# H204_R_Power.net
KiCad netlist of a schematic drawn in Altium Designer
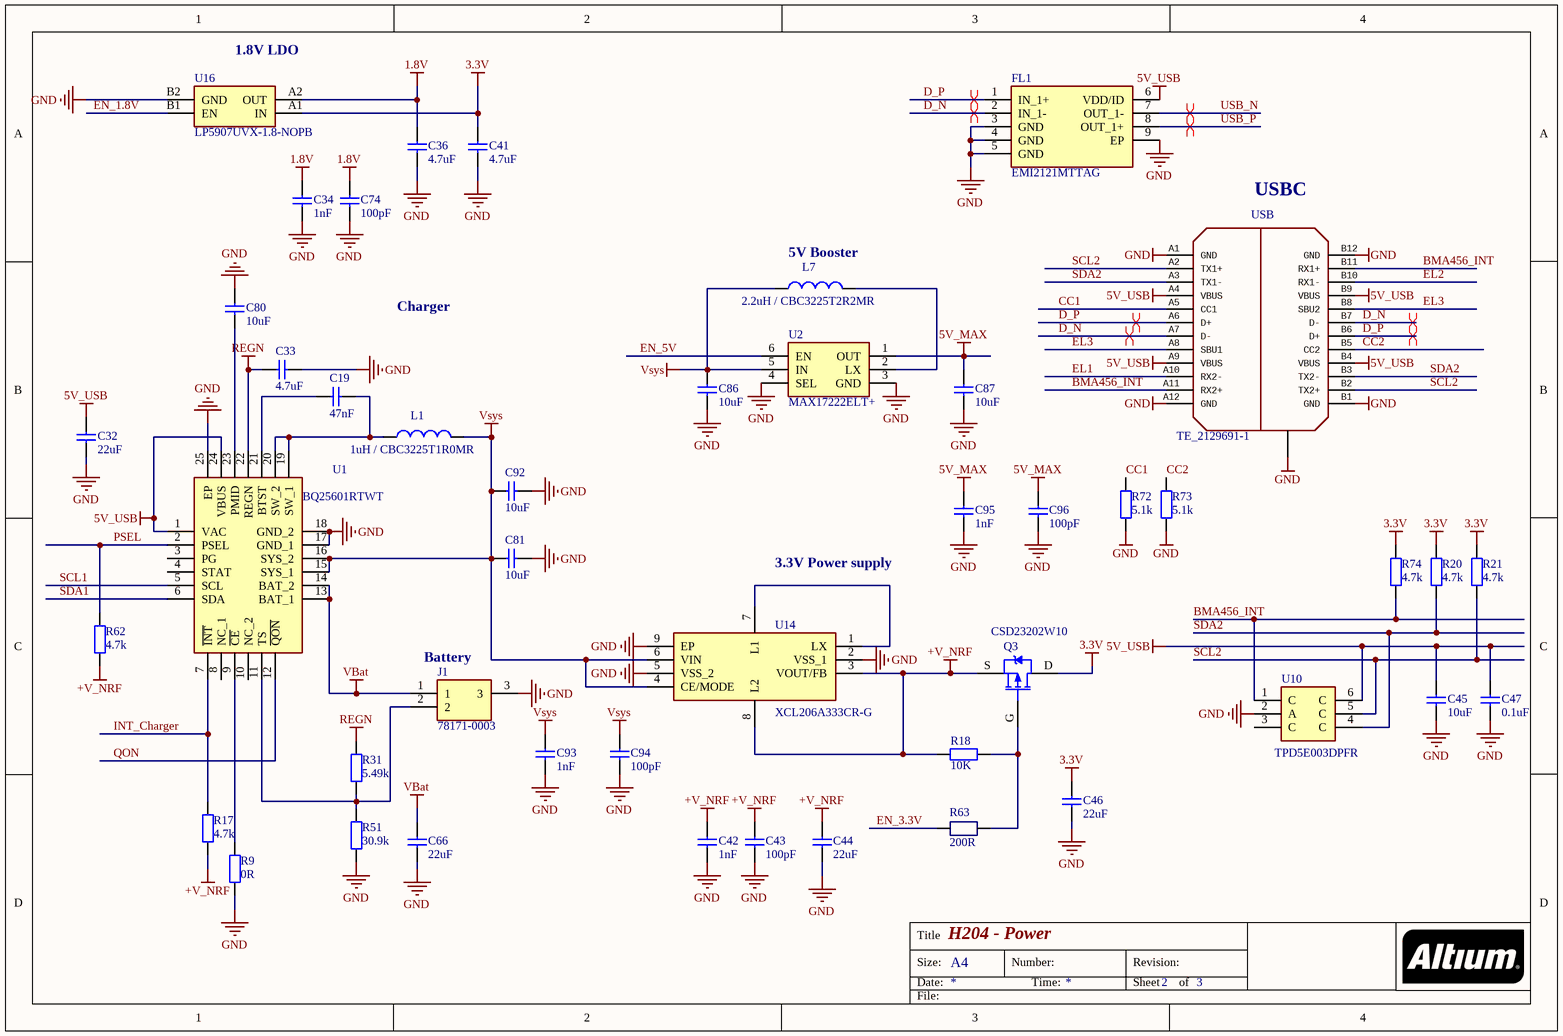
[diagram p0: H204_R_Power.SchDoc]

(export (version "E")
  (design (tool "Eeschema 10.0.6"))
  (components
    (comp (ref "C19")
      (value "47nF")
      (footprint "CAPC0603X33N")
      (description "CAP CER 0.047UF 25V X5R 0201")
      (fields
        (field (name "MANUFACTURER") "TDK")
        (field (name "MANUFACTURER PART NUMBER") "C0603X5R1E473K030BB")
      )
      (libsource (lib "Nordic Passive DB") (part "CAP"))
    )
    (comp (ref "C32")
      (value "22uF")
      (footprint "CAPC1005X55N")
      (description "CAP CER 22UF 6.3V X5R 0402")
      (fields
        (field (name "MANUFACTURER") "Samsung")
        (field (name "MANUFACTURER PART NUMBER") "CL05A226MQ5QUNC")
      )
      (libsource (lib "Nordic Passive DB") (part "CAP"))
    )
    (comp (ref "C33")
      (value "4.7uF")
      (footprint "CAPC1005X55N")
      (description "Cap Ceramic 4.7uF 16V X5R 20% SMD 0402 85C T/R")
      (fields
        (field (name "MANUFACTURER") "Samsung")
        (field (name "MANUFACTURER PART NUMBER") "CL05A475MO5NUNC")
      )
      (libsource (lib "Nordic Passive DB") (part "CAP"))
    )
    (comp (ref "C34")
      (value "1nF")
      (footprint "CAPC0603X33N")
      (description "Cap Ceramic 0.001uF 25V X7R 10% SMD 0201 125C Paper T/R")
      (fields
        (field (name "MANUFACTURER") "Samsung")
        (field (name "MANUFACTURER PART NUMBER") "CL03B102KA3NNNC")
      )
      (libsource (lib "Nordic Passive DB") (part "CAP"))
    )
    (comp (ref "C36")
      (value "4.7uF")
      (footprint "CAPC1005X55N")
      (description "Cap Ceramic 4.7uF 16V X5R 20% SMD 0402 85C T/R")
      (fields
        (field (name "MANUFACTURER") "Samsung")
        (field (name "MANUFACTURER PART NUMBER") "CL05A475MO5NUNC")
      )
      (libsource (lib "Nordic Passive DB") (part "CAP"))
    )
    (comp (ref "C41")
      (value "4.7uF")
      (footprint "CAPC1005X55N")
      (description "Cap Ceramic 4.7uF 16V X5R 20% SMD 0402 85C T/R")
      (fields
        (field (name "MANUFACTURER") "Samsung")
        (field (name "MANUFACTURER PART NUMBER") "CL05A475MO5NUNC")
      )
      (libsource (lib "Nordic Passive DB") (part "CAP"))
    )
    (comp (ref "C42")
      (value "1nF")
      (footprint "CAPC0603X33N")
      (description "Cap Ceramic 0.001uF 25V X7R 10% SMD 0201 125C Paper T/R")
      (fields
        (field (name "MANUFACTURER") "Samsung")
        (field (name "MANUFACTURER PART NUMBER") "CL03B102KA3NNNC")
      )
      (libsource (lib "Nordic Passive DB") (part "CAP"))
    )
    (comp (ref "C43")
      (value "100pF")
      (footprint "CAPC0603X33N")
      (description "CAP CER 100PF 50V C0G 0201")
      (fields
        (field (name "MANUFACTURER") "TDK")
        (field (name "MANUFACTURER PART NUMBER") "C0603C0G1H101J030BA")
      )
      (libsource (lib "Nordic Passive DB") (part "CAP"))
    )
    (comp (ref "C44")
      (value "22uF")
      (footprint "CAPC1005X55N")
      (description "CAP CER 22UF 6.3V X5R 0402")
      (fields
        (field (name "MANUFACTURER") "Samsung")
        (field (name "MANUFACTURER PART NUMBER") "CL05A226MQ5QUNC")
      )
      (libsource (lib "Nordic Passive DB") (part "CAP"))
    )
    (comp (ref "C45")
      (value "10uF")
      (footprint "CAPC1005X55N")
      (description "CAP CER 10UF 10V X5R 0402")
      (fields
        (field (name "MANUFACTURER") "Samsung")
        (field (name "MANUFACTURER PART NUMBER") "CL05A106MP8NUB8")
      )
      (libsource (lib "Nordic Passive DB") (part "CAP"))
    )
    (comp (ref "C46")
      (value "22uF")
      (footprint "CAPC1005X55N")
      (description "CAP CER 22UF 6.3V X5R 0402")
      (fields
        (field (name "MANUFACTURER") "Samsung")
        (field (name "MANUFACTURER PART NUMBER") "CL05A226MQ5QUNC")
      )
      (libsource (lib "Nordic Passive DB") (part "CAP"))
    )
    (comp (ref "C47")
      (value "0.1uF")
      (footprint "CAPC0603X33N")
      (description "CAP CER 0.1UF 16V X5R 0201")
      (fields
        (field (name "MANUFACTURER") "Samsung")
        (field (name "MANUFACTURER PART NUMBER") "CL03A104KO3NNNC")
      )
      (libsource (lib "AltiumLib") (part "CAP"))
    )
    (comp (ref "C66")
      (value "22uF")
      (footprint "CAPC1005X55N")
      (description "CAP CER 22UF 6.3V X5R 0402")
      (fields
        (field (name "MANUFACTURER") "Samsung")
        (field (name "MANUFACTURER PART NUMBER") "CL05A226MQ5QUNC")
      )
      (libsource (lib "Nordic Passive DB") (part "CAP"))
    )
    (comp (ref "C74")
      (value "100pF")
      (footprint "CAPC0603X33N")
      (description "CAP CER 100PF 50V C0G 0201")
      (fields
        (field (name "MANUFACTURER") "TDK")
        (field (name "MANUFACTURER PART NUMBER") "C0603C0G1H101J030BA")
      )
      (libsource (lib "Nordic Passive DB") (part "CAP"))
    )
    (comp (ref "C80")
      (value "10uF")
      (footprint "CAPC1005X55N")
      (description "CAP CER 10UF 10V X5R 0402")
      (fields
        (field (name "MANUFACTURER") "Samsung")
        (field (name "MANUFACTURER PART NUMBER") "CL05A106MP8NUB8")
      )
      (libsource (lib "Nordic Passive DB") (part "CAP"))
    )
    (comp (ref "C81")
      (value "10uF")
      (footprint "CAPC1005X55N")
      (description "CAP CER 10UF 10V X5R 0402")
      (fields
        (field (name "MANUFACTURER") "Samsung")
        (field (name "MANUFACTURER PART NUMBER") "CL05A106MP8NUB8")
      )
      (libsource (lib "Nordic Passive DB") (part "CAP"))
    )
    (comp (ref "C86")
      (value "10uF")
      (footprint "CAPC1005X55N")
      (description "CAP CER 10UF 10V X5R 0402")
      (fields
        (field (name "MANUFACTURER") "Samsung")
        (field (name "MANUFACTURER PART NUMBER") "CL05A106MP8NUB8")
      )
      (libsource (lib "Nordic Passive DB") (part "CAP"))
    )
    (comp (ref "C87")
      (value "10uF")
      (footprint "CAPC1005X55N")
      (description "CAP CER 10UF 10V X5R 0402")
      (fields
        (field (name "MANUFACTURER") "Samsung")
        (field (name "MANUFACTURER PART NUMBER") "CL05A106MP8NUB8")
      )
      (libsource (lib "Nordic Passive DB") (part "CAP"))
    )
    (comp (ref "C92")
      (value "10uF")
      (footprint "CAPC1005X55N")
      (description "CAP CER 10UF 10V X5R 0402")
      (fields
        (field (name "MANUFACTURER") "Samsung")
        (field (name "MANUFACTURER PART NUMBER") "CL05A106MP8NUB8")
      )
      (libsource (lib "Nordic Passive DB") (part "CAP"))
    )
    (comp (ref "C93")
      (value "1nF")
      (footprint "CAPC0603X33N")
      (description "Cap Ceramic 0.001uF 25V X7R 10% SMD 0201 125C Paper T/R")
      (fields
        (field (name "MANUFACTURER") "Samsung")
        (field (name "MANUFACTURER PART NUMBER") "CL03B102KA3NNNC")
      )
      (libsource (lib "Nordic Passive DB") (part "CAP"))
    )
    (comp (ref "C94")
      (value "100pF")
      (footprint "CAPC0603X33N")
      (description "CAP CER 100PF 50V C0G 0201")
      (fields
        (field (name "MANUFACTURER") "TDK")
        (field (name "MANUFACTURER PART NUMBER") "C0603C0G1H101J030BA")
      )
      (libsource (lib "Nordic Passive DB") (part "CAP"))
    )
    (comp (ref "C95")
      (value "1nF")
      (footprint "CAPC0603X33N")
      (description "Cap Ceramic 0.001uF 25V X7R 10% SMD 0201 125C Paper T/R")
      (fields
        (field (name "MANUFACTURER") "Samsung")
        (field (name "MANUFACTURER PART NUMBER") "CL03B102KA3NNNC")
      )
      (libsource (lib "Nordic Passive DB") (part "CAP"))
    )
    (comp (ref "C96")
      (value "100pF")
      (footprint "CAPC0603X33N")
      (description "CAP CER 100PF 50V C0G 0201")
      (fields
        (field (name "MANUFACTURER") "TDK")
        (field (name "MANUFACTURER PART NUMBER") "C0603C0G1H101J030BA")
      )
      (libsource (lib "Nordic Passive DB") (part "CAP"))
    )
    (comp (ref "FL1")
      (value "EMI2121MTTAG")
      (footprint "EMI2121MTTAG")
      (description "ON SEMICONDUCTOR - EMI2121MTTAG - Common Mode Filter, USB 2.0, WDFN-8")
      (fields (field (name "MANUFACTURER") "ON Semiconductor"))
      (libsource (lib "*") (part "EMI2121MTTAG"))
    )
    (comp (ref "J1")
      (value "78171-0003")
      (footprint "SamacSys:78171-0003")
      (description "Conn Wire to Board HDR 3 POS 1.2mm Solder ST SMD Embossed T/R")
      (fields (field (name "MOUSER PART NUMBER") "538-78171-0003") (field (name "MANUFACTURER") "Molex"))
      (libsource (lib "*") (part "78171-0003"))
    )
    (comp (ref "L1")
      (value "1uH / CBC3225T1R0MR")
      (footprint "INDM3225X210N")
      (description "Inductor Power Chip Wirewound 1uH 20% 100KHz Ferrite 1.44A 71.5mOhm DCR 1210 T/R")
      (fields
        (field (name "MANUFACTURER") "Taiyo Yuden")
        (field (name "MANUFACTURER PART NUMBER") "CBC3225T2R2MR")
      )
      (libsource (lib "Inductors") (part "Inductor"))
    )
    (comp (ref "L7")
      (value "2.2uH / CBC3225T2R2MR")
      (footprint "INDM3225X210N")
      (description "Ind Power Chip Wirewound 2.2uH 20% 100KHz Ferrite 1.13A 1210 T/R")
      (fields
        (field (name "MANUFACTURER") "Taiyo Yuden")
        (field (name "MANUFACTURER PART NUMBER") "CBC3225T2R2MR")
      )
      (libsource (lib "Inductors") (part "Inductor"))
    )
    (comp (ref "Q3")
      (value "CSD23202W10")
      (footprint "4-UFBGA")
      (description "-12V, P ch NexFET MOSFET™, single WLP 1.0x1.0, 53mOhm 4-DSBGA")
      (fields (field (name "MANUFACTURER") "Texas Instruments"))
      (libsource (lib "Transistors") (part "Transistor P-channel"))
    )
    (comp (ref "R9")
      (value "0R")
      (footprint "RESC0603X26N")
      (description "Fixed Resistor, Metal Glaze/thick Film, 0.05W, 0ohm, Surface Mount, 0201")
      (fields
        (field (name "MANUFACTURER") "Yageo")
        (field (name "MANUFACTURER PART NUMBER") "AF0201JR-070RL")
      )
      (libsource (lib "") (part "Res2_1"))
    )
    (comp (ref "R17")
      (value "4.7k")
      (footprint "RESC0603X26N")
      (description "GENERAL 0201 11% REEL (7INCH)")
      (fields
        (field (name "MANUFACTURER") "Yageo")
        (field (name "MANUFACTURER PART NUMBER") "RC0201FR-074K7L")
      )
      (libsource (lib "Miscellaneous Devices") (part "Res2"))
    )
    (comp (ref "R18")
      (value "10K")
      (footprint "RESC0603X26N")
      (description "GENERAL 0201 11% REEL (7INCH)")
      (fields
        (field (name "MANUFACTURER") "Yageo")
        (field (name "MANUFACTURER PART NUMBER") "RC0201FR-0710KL")
      )
      (libsource (lib "Miscellaneous Devices") (part "Res2"))
    )
    (comp (ref "R20")
      (value "4.7k")
      (footprint "RESC0603X26N")
      (description "GENERAL 0201 11% REEL (7INCH)")
      (fields
        (field (name "MANUFACTURER") "Yageo")
        (field (name "MANUFACTURER PART NUMBER") "RC0201FR-074K7L")
      )
      (libsource (lib "Miscellaneous Devices") (part "Res2"))
    )
    (comp (ref "R21")
      (value "4.7k")
      (footprint "RESC0603X26N")
      (description "GENERAL 0201 11% REEL (7INCH)")
      (fields
        (field (name "MANUFACTURER") "Yageo")
        (field (name "MANUFACTURER PART NUMBER") "RC0201FR-074K7L")
      )
      (libsource (lib "Miscellaneous Devices") (part "Res2"))
    )
    (comp (ref "R31")
      (value "5.49k")
      (footprint "RESC0603X26N")
      (description "RES SMD 5.49K OHM 1% 1/20W 0201")
      (fields
        (field (name "MANUFACTURER") "Yageo")
        (field (name "MANUFACTURER PART NUMBER") "RC0201FR-075K49L")
      )
      (libsource (lib "Miscellaneous Devices") (part "Res2"))
    )
    (comp (ref "R51")
      (value "30.9k")
      (footprint "RESC0603X26N")
      (description "Res Thick Film 0201 30.9K Ohm 1% 0.05W(1/20W) ±200ppm/C Molded SMD Paper T/R")
      (fields
        (field (name "MANUFACTURER") "Yageo")
        (field (name "MANUFACTURER PART NUMBER") "RC0201FR-0730K9L")
      )
      (libsource (lib "Miscellaneous Devices") (part "Res2"))
    )
    (comp (ref "R62")
      (value "4.7k")
      (footprint "RESC0603X26N")
      (description "GENERAL 0201 11% REEL (7INCH)")
      (fields
        (field (name "MANUFACTURER") "Yageo")
        (field (name "MANUFACTURER PART NUMBER") "RC0201FR-074K7L")
      )
      (libsource (lib "Miscellaneous Devices") (part "Res2"))
    )
    (comp (ref "R63")
      (value "200R")
      (footprint "RESC0603X26N")
      (description "RES SMD 200 OHM 1% 1/20W 0201")
      (fields
        (field (name "MANUFACTURER") "Yageo")
        (field (name "MANUFACTURER PART NUMBER") "RC0201FR-07200RL")
      )
      (libsource (lib "Passive components") (part "Resistor"))
    )
    (comp (ref "R72")
      (value "5.1k")
      (footprint "RESC0603X26N")
      (description "Res Thick Film 0201 5.1K Ohm 1% 1/20W ±200ppm/°C Molded SMD Paper T/R")
      (fields
        (field (name "MANUFACTURER") "Yageo")
        (field (name "MANUFACTURER PART NUMBER") "RC0201FR-075K1L")
      )
      (libsource (lib "Miscellaneous Devices") (part "Res2"))
    )
    (comp (ref "R73")
      (value "5.1k")
      (footprint "RESC0603X26N")
      (description "Res Thick Film 0201 5.1K Ohm 1% 1/20W ±200ppm/°C Molded SMD Paper T/R")
      (fields
        (field (name "MANUFACTURER") "Yageo")
        (field (name "MANUFACTURER PART NUMBER") "RC0201FR-075K1L")
      )
      (libsource (lib "Miscellaneous Devices") (part "Res2"))
    )
    (comp (ref "R74")
      (value "4.7k")
      (footprint "RESC0603X26N")
      (description "GENERAL 0201 11% REEL (7INCH)")
      (fields
        (field (name "MANUFACTURER") "Yageo")
        (field (name "MANUFACTURER PART NUMBER") "RC0201FR-074K7L")
      )
      (libsource (lib "Miscellaneous Devices") (part "Res2"))
    )
    (comp (ref "U1")
      (value "BQ25601RTWT")
      (footprint "SamacSys:QFN50P400X400X80-25N-D")
      (description "IC BATTERY CHARGER LION 24WQFN")
      (fields (field (name "MANUFACTURER") "Texas Instruments"))
      (libsource (lib "*") (part "BQ25601DRTWR"))
    )
    (comp (ref "U2")
      (value "MAX17222ELT+")
      (footprint "SamacSys:MAX17220ALT")
      (description "Conv DC-DC Single Step Up 0.4V to 5.5V 6-Pin uDFN Cut Tape")
      (fields (field (name "MOUSER PART NUMBER") "700-MAX17222ELT+") (field (name "MANUFACTURER") "Maxim"))
      (libsource (lib "*") (part "MAX17222ELT+"))
    )
    (comp (ref "U10")
      (value "TPD5E003DPFR")
      (footprint "SON35P100X100X40-6N")
      (description "ESD Suppressors Five CH Space Saving ESD Protect Device")
      (fields (field (name "MANUFACTURER") "Texas Instruments"))
      (libsource (lib "*") (part "SP0505BAJTG"))
    )
    (comp (ref "U14")
      (value "XCL206A333CR-G")
      (footprint "XCL206A333CRG")
      (description "Conv DC-DC Single Step Down 2V to 6V 6-Pin CL-2025-02 T/R")
      (fields (field (name "MOUSER PART NUMBER") "865-XCL206A333CR-G") (field (name "MANUFACTURER") "Torex"))
      (libsource (lib "*") (part "XCL206A333CR-G"))
    )
    (comp (ref "U16")
      (value "LP5907UVX-1.8-NOPB")
      (footprint "BGA4C35P2X2_64X64X44")
      (description "IC REG LINEAR 1.8V 250MA 4DSBGA")
      (fields
        (field (name "MANUFACTURER") "Texas Instruments")
        (field (name "MANUFACTURER PART NUMBER") "LP5907UVX-1.8/NOPB")
      )
      (libsource (lib "*") (part "LP5907UVX-1.6_NOPB"))
    )
    (comp (ref "USB")
      (value "TE_2129691-1")
      (footprint "TE_2129691-1")
      (description "TE CONNECTIVITY         2129691-1             USB, 3.1 TYPE C, 24POS, RCPT, SMT/TH")
      (fields
        (field (name "MANUFACTURER") "TE Connectivity AMP")
        (field (name "MANUFACTURER PART NUMBER") "2129691-1")
      )
      (libsource (lib "SparkFun-Connectors") (part "1054500101"))
    )
  )
  (nets
    (net (code "1") (name "+V_NRF") (class "Default")
      (node (ref "C42") (pin "2") (pinfunction "2_2") (pintype "passive"))
      (node (ref "C43") (pin "1") (pinfunction "1_1") (pintype "passive"))
      (node (ref "C44") (pin "1") (pinfunction "1_1") (pintype "passive"))
      (node (ref "Q3") (pin "S") (pinfunction "S_S") (pintype "passive"))
      (node (ref "R17") (pin "2") (pinfunction "2_2") (pintype "passive"))
      (node (ref "R18") (pin "2") (pinfunction "2_2") (pintype "passive"))
      (node (ref "R62") (pin "2") (pinfunction "2_2") (pintype "passive"))
      (node (ref "U14") (pin "3") (pinfunction "VOUT/FB_3") (pintype "passive"))
      (node (ref "U14") (pin "8") (pinfunction "L2_8") (pintype "passive"))
    )
    (net (code "2") (name "/BMA456_INT") (class "Default")
      (node (ref "R74") (pin "2") (pinfunction "2_2") (pintype "passive"))
      (node (ref "U10") (pin "1") (pinfunction "C_1") (pintype "passive"))
      (node (ref "USB") (pin "A11") (pinfunction "RX2+_A11") (pintype "passive"))
      (node (ref "USB") (pin "B11") (pinfunction "RX1+_B11") (pintype "passive"))
    )
    (net (code "3") (name "/CC1") (class "Default")
      (node (ref "R72") (pin "1") (pinfunction "1_1") (pintype "passive"))
      (node (ref "USB") (pin "A5") (pinfunction "CC1_A5") (pintype "passive"))
    )
    (net (code "4") (name "/CC2") (class "Default")
      (node (ref "R73") (pin "1") (pinfunction "1_1") (pintype "passive"))
      (node (ref "USB") (pin "B5") (pinfunction "CC2_B5") (pintype "passive"))
    )
    (net (code "5") (name "/D_N") (class "Default")
      (node (ref "FL1") (pin "2") (pinfunction "IN_1-_2") (pintype "passive"))
      (node (ref "USB") (pin "A7") (pinfunction "D-_A7") (pintype "passive"))
      (node (ref "USB") (pin "B7") (pinfunction "D-_B7") (pintype "passive"))
    )
    (net (code "6") (name "/D_P") (class "Default")
      (node (ref "FL1") (pin "1") (pinfunction "IN_1+_1") (pintype "passive"))
      (node (ref "USB") (pin "A6") (pinfunction "D+_A6") (pintype "passive"))
      (node (ref "USB") (pin "B6") (pinfunction "D+_B6") (pintype "passive"))
    )
    (net (code "7") (name "/EL1") (class "Default")
      (node (ref "USB") (pin "A10") (pinfunction "RX2-_A10") (pintype "passive"))
    )
    (net (code "8") (name "/EL2") (class "Default")
      (node (ref "USB") (pin "B10") (pinfunction "RX1-_B10") (pintype "passive"))
    )
    (net (code "9") (name "/EL3") (class "Default")
      (node (ref "USB") (pin "A8") (pinfunction "SBU1_A8") (pintype "passive"))
      (node (ref "USB") (pin "B8") (pinfunction "SBU2_B8") (pintype "passive"))
    )
    (net (code "10") (name "/EN_1.8V") (class "Default")
      (node (ref "U16") (pin "B1") (pinfunction "EN_B1") (pintype "passive"))
    )
    (net (code "11") (name "/EN_3.3V") (class "Default")
      (node (ref "R63") (pin "1") (pinfunction "1_1") (pintype "passive"))
    )
    (net (code "12") (name "/EN_5V") (class "Default")
      (node (ref "U2") (pin "6") (pinfunction "EN_6") (pintype "passive"))
    )
    (net (code "13") (name "/INT_Charger") (class "Default")
      (node (ref "R17") (pin "1") (pinfunction "1_1") (pintype "passive"))
      (node (ref "U1") (pin "7") (pinfunction "~{INT}_7") (pintype "passive"))
    )
    (net (code "14") (name "/PSEL") (class "Default")
      (node (ref "R62") (pin "1") (pinfunction "1_1") (pintype "passive"))
      (node (ref "U1") (pin "2") (pinfunction "PSEL_2") (pintype "passive"))
    )
    (net (code "15") (name "/QON") (class "Default")
      (node (ref "U1") (pin "12") (pinfunction "~{QON}_12") (pintype "passive"))
    )
    (net (code "16") (name "/SCL1") (class "Default")
      (node (ref "U1") (pin "5") (pinfunction "SCL_5") (pintype "passive"))
    )
    (net (code "17") (name "/SCL2") (class "Default")
      (node (ref "R21") (pin "2") (pinfunction "2_2") (pintype "passive"))
      (node (ref "U10") (pin "5") (pinfunction "C_5") (pintype "passive"))
      (node (ref "USB") (pin "A2") (pinfunction "TX1+_A2") (pintype "passive"))
      (node (ref "USB") (pin "B2") (pinfunction "TX2+_B2") (pintype "passive"))
    )
    (net (code "18") (name "/SDA1") (class "Default")
      (node (ref "U1") (pin "6") (pinfunction "SDA_6") (pintype "passive"))
    )
    (net (code "19") (name "/SDA2") (class "Default")
      (node (ref "R20") (pin "2") (pinfunction "2_2") (pintype "passive"))
      (node (ref "U10") (pin "4") (pinfunction "C_4") (pintype "passive"))
      (node (ref "USB") (pin "A3") (pinfunction "TX1-_A3") (pintype "passive"))
      (node (ref "USB") (pin "B3") (pinfunction "TX2-_B3") (pintype "passive"))
    )
    (net (code "20") (name "/USB_N") (class "Default")
      (node (ref "FL1") (pin "7") (pinfunction "OUT_1-_7") (pintype "passive"))
    )
    (net (code "21") (name "/USB_P") (class "Default")
      (node (ref "FL1") (pin "8") (pinfunction "OUT_1+_8") (pintype "passive"))
    )
    (net (code "22") (name "1.8V") (class "Default")
      (node (ref "C34") (pin "1") (pinfunction "1_1") (pintype "passive"))
      (node (ref "C36") (pin "1") (pinfunction "1_1") (pintype "passive"))
      (node (ref "C74") (pin "1") (pinfunction "1_1") (pintype "passive"))
      (node (ref "U16") (pin "A2") (pinfunction "OUT_A2") (pintype "passive"))
    )
    (net (code "23") (name "3.3V") (class "Default")
      (node (ref "C41") (pin "1") (pinfunction "1_1") (pintype "passive"))
      (node (ref "C46") (pin "1") (pinfunction "1_1") (pintype "passive"))
      (node (ref "Q3") (pin "D") (pinfunction "D_D") (pintype "passive"))
      (node (ref "R20") (pin "1") (pinfunction "1_1") (pintype "passive"))
      (node (ref "R21") (pin "1") (pinfunction "1_1") (pintype "passive"))
      (node (ref "R74") (pin "1") (pinfunction "1_1") (pintype "passive"))
      (node (ref "U16") (pin "A1") (pinfunction "IN_A1") (pintype "passive"))
    )
    (net (code "24") (name "5V_MAX") (class "Default")
      (node (ref "C87") (pin "1") (pinfunction "1_1") (pintype "passive"))
      (node (ref "C95") (pin "1") (pinfunction "1_1") (pintype "passive"))
      (node (ref "C96") (pin "1") (pinfunction "1_1") (pintype "passive"))
      (node (ref "U2") (pin "1") (pinfunction "OUT_1") (pintype "passive"))
    )
    (net (code "25") (name "5V_USB") (class "Default")
      (node (ref "C32") (pin "1") (pinfunction "1_1") (pintype "passive"))
      (node (ref "C45") (pin "1") (pinfunction "1_1") (pintype "passive"))
      (node (ref "C47") (pin "1") (pinfunction "1_1") (pintype "passive"))
      (node (ref "FL1") (pin "6") (pinfunction "VDD/ID_6") (pintype "passive"))
      (node (ref "U1") (pin "1") (pinfunction "VAC_1") (pintype "passive"))
      (node (ref "U1") (pin "24") (pinfunction "VBUS_24") (pintype "passive"))
      (node (ref "U10") (pin "6") (pinfunction "C_6") (pintype "passive"))
      (node (ref "USB") (pin "A4") (pinfunction "VBUS_A4") (pintype "passive"))
      (node (ref "USB") (pin "A9") (pinfunction "VBUS_A9") (pintype "passive"))
      (node (ref "USB") (pin "B4") (pinfunction "VBUS_B4") (pintype "passive"))
      (node (ref "USB") (pin "B9") (pinfunction "VBUS_B9") (pintype "passive"))
    )
    (net (code "26") (name "GND") (class "Default")
      (node (ref "C32") (pin "2") (pinfunction "2_2") (pintype "passive"))
      (node (ref "C33") (pin "2") (pinfunction "2_2") (pintype "passive"))
      (node (ref "C34") (pin "2") (pinfunction "2_2") (pintype "passive"))
      (node (ref "C36") (pin "2") (pinfunction "2_2") (pintype "passive"))
      (node (ref "C41") (pin "2") (pinfunction "2_2") (pintype "passive"))
      (node (ref "C42") (pin "1") (pinfunction "1_1") (pintype "passive"))
      (node (ref "C43") (pin "2") (pinfunction "2_2") (pintype "passive"))
      (node (ref "C44") (pin "2") (pinfunction "2_2") (pintype "passive"))
      (node (ref "C45") (pin "2") (pinfunction "2_2") (pintype "passive"))
      (node (ref "C46") (pin "2") (pinfunction "2_2") (pintype "passive"))
      (node (ref "C47") (pin "2") (pinfunction "2_2") (pintype "passive"))
      (node (ref "C66") (pin "2") (pinfunction "2_2") (pintype "passive"))
      (node (ref "C74") (pin "2") (pinfunction "2_2") (pintype "passive"))
      (node (ref "C80") (pin "2") (pinfunction "2_2") (pintype "passive"))
      (node (ref "C81") (pin "2") (pinfunction "2_2") (pintype "passive"))
      (node (ref "C86") (pin "2") (pinfunction "2_2") (pintype "passive"))
      (node (ref "C87") (pin "2") (pinfunction "2_2") (pintype "passive"))
      (node (ref "C92") (pin "2") (pinfunction "2_2") (pintype "passive"))
      (node (ref "C93") (pin "2") (pinfunction "2_2") (pintype "passive"))
      (node (ref "C94") (pin "2") (pinfunction "2_2") (pintype "passive"))
      (node (ref "C95") (pin "2") (pinfunction "2_2") (pintype "passive"))
      (node (ref "C96") (pin "2") (pinfunction "2_2") (pintype "passive"))
      (node (ref "FL1") (pin "3") (pinfunction "GND_3") (pintype "passive"))
      (node (ref "FL1") (pin "4") (pinfunction "GND_4") (pintype "passive"))
      (node (ref "FL1") (pin "5") (pinfunction "GND_5") (pintype "passive"))
      (node (ref "FL1") (pin "9") (pinfunction "EP_9") (pintype "passive"))
      (node (ref "J1") (pin "3") (pinfunction "3_3") (pintype "passive"))
      (node (ref "R51") (pin "2") (pinfunction "2_2") (pintype "passive"))
      (node (ref "R72") (pin "2") (pinfunction "2_2") (pintype "passive"))
      (node (ref "R73") (pin "2") (pinfunction "2_2") (pintype "passive"))
      (node (ref "R9") (pin "1") (pinfunction "1_1") (pintype "passive"))
      (node (ref "U1") (pin "17") (pinfunction "GND_1_17") (pintype "passive"))
      (node (ref "U1") (pin "18") (pinfunction "GND_2_18") (pintype "passive"))
      (node (ref "U1") (pin "25") (pinfunction "EP_25") (pintype "passive"))
      (node (ref "U10") (pin "2") (pinfunction "A_2") (pintype "passive"))
      (node (ref "U14") (pin "2") (pinfunction "VSS_1_2") (pintype "passive"))
      (node (ref "U14") (pin "5") (pinfunction "VSS_2_5") (pintype "passive"))
      (node (ref "U14") (pin "9") (pinfunction "EP_9") (pintype "passive"))
      (node (ref "U16") (pin "B2") (pinfunction "GND_B2") (pintype "passive"))
      (node (ref "U2") (pin "3") (pinfunction "GND_3") (pintype "passive"))
      (node (ref "U2") (pin "4") (pinfunction "SEL_4") (pintype "passive"))
      (node (ref "USB") (pin "A1") (pinfunction "GND_A1") (pintype "passive"))
      (node (ref "USB") (pin "A12") (pinfunction "GND_A12") (pintype "passive"))
      (node (ref "USB") (pin "B1") (pinfunction "GND_B1") (pintype "passive"))
      (node (ref "USB") (pin "B12") (pinfunction "GND_B12") (pintype "passive"))
      (node (ref "USB") (pin "SH") (pinfunction "SH_SH") (pintype "passive"))
    )
    (net (code "27") (name "Net-(Q3-PadG)") (class "Default")
      (node (ref "Q3") (pin "G") (pinfunction "G_G") (pintype "passive"))
      (node (ref "R18") (pin "1") (pinfunction "1_1") (pintype "passive"))
      (node (ref "R63") (pin "2") (pinfunction "2_2") (pintype "passive"))
    )
    (net (code "28") (name "Net-(U1-BTST)") (class "Default")
      (node (ref "C19") (pin "2") (pinfunction "2_2") (pintype "passive"))
      (node (ref "U1") (pin "21") (pinfunction "BTST_21") (pintype "passive"))
    )
    (net (code "29") (name "Net-(U1-PMID)") (class "Default")
      (node (ref "C80") (pin "1") (pinfunction "1_1") (pintype "passive"))
      (node (ref "U1") (pin "23") (pinfunction "PMID_23") (pintype "passive"))
    )
    (net (code "30") (name "Net-(U1-SW_1)") (class "Default")
      (node (ref "C19") (pin "1") (pinfunction "1_1") (pintype "passive"))
      (node (ref "L1") (pin "1") (pinfunction "1_1") (pintype "passive"))
      (node (ref "U1") (pin "19") (pinfunction "SW_1_19") (pintype "passive"))
      (node (ref "U1") (pin "20") (pinfunction "SW_2_20") (pintype "passive"))
    )
    (net (code "31") (name "Net-(U1-TS)") (class "Default")
      (node (ref "J1") (pin "2") (pinfunction "2_2") (pintype "passive"))
      (node (ref "R31") (pin "2") (pinfunction "2_2") (pintype "passive"))
      (node (ref "R51") (pin "1") (pinfunction "1_1") (pintype "passive"))
      (node (ref "U1") (pin "11") (pinfunction "TS_11") (pintype "passive"))
    )
    (net (code "32") (name "Net-(U1-~{CE})") (class "Default")
      (node (ref "R9") (pin "2") (pinfunction "2_2") (pintype "passive"))
      (node (ref "U1") (pin "9") (pinfunction "~{CE}_9") (pintype "passive"))
    )
    (net (code "33") (name "Net-(U2-LX)") (class "Default")
      (node (ref "L7") (pin "2") (pinfunction "2_2") (pintype "passive"))
      (node (ref "U2") (pin "2") (pinfunction "LX_2") (pintype "passive"))
    )
    (net (code "34") (name "Net-(U14-L1)") (class "Default")
      (node (ref "U14") (pin "1") (pinfunction "LX_1") (pintype "passive"))
      (node (ref "U14") (pin "7") (pinfunction "L1_7") (pintype "passive"))
    )
    (net (code "35") (name "REGN") (class "Default")
      (node (ref "C33") (pin "1") (pinfunction "1_1") (pintype "passive"))
      (node (ref "R31") (pin "1") (pinfunction "1_1") (pintype "passive"))
      (node (ref "U1") (pin "22") (pinfunction "REGN_22") (pintype "passive"))
    )
    (net (code "36") (name "VBat") (class "Default")
      (node (ref "C66") (pin "1") (pinfunction "1_1") (pintype "passive"))
      (node (ref "J1") (pin "1") (pinfunction "1_1") (pintype "passive"))
      (node (ref "U1") (pin "13") (pinfunction "BAT_1_13") (pintype "passive"))
      (node (ref "U1") (pin "14") (pinfunction "BAT_2_14") (pintype "passive"))
    )
    (net (code "37") (name "Vsys") (class "Default")
      (node (ref "C81") (pin "1") (pinfunction "1_1") (pintype "passive"))
      (node (ref "C86") (pin "1") (pinfunction "1_1") (pintype "passive"))
      (node (ref "C92") (pin "1") (pinfunction "1_1") (pintype "passive"))
      (node (ref "C93") (pin "1") (pinfunction "1_1") (pintype "passive"))
      (node (ref "C94") (pin "1") (pinfunction "1_1") (pintype "passive"))
      (node (ref "L1") (pin "2") (pinfunction "2_2") (pintype "passive"))
      (node (ref "L7") (pin "1") (pinfunction "1_1") (pintype "passive"))
      (node (ref "U1") (pin "15") (pinfunction "SYS_1_15") (pintype "passive"))
      (node (ref "U1") (pin "16") (pinfunction "SYS_2_16") (pintype "passive"))
      (node (ref "U14") (pin "4") (pinfunction "CE/MODE_4") (pintype "passive"))
      (node (ref "U14") (pin "6") (pinfunction "VIN_6") (pintype "passive"))
      (node (ref "U2") (pin "5") (pinfunction "IN_5") (pintype "passive"))
    )
    (net (code "38") (name "unconnected-(U1-NC_1-Pad8)") (class "Default")
      (node (ref "U1") (pin "8") (pinfunction "NC_1_8") (pintype "passive"))
    )
    (net (code "39") (name "unconnected-(U1-NC_2-Pad10)") (class "Default")
      (node (ref "U1") (pin "10") (pinfunction "NC_2_10") (pintype "passive"))
    )
    (net (code "40") (name "unconnected-(U1-PG-Pad3)") (class "Default")
      (node (ref "U1") (pin "3") (pinfunction "PG_3") (pintype "passive"))
    )
    (net (code "41") (name "unconnected-(U1-STAT-Pad4)") (class "Default")
      (node (ref "U1") (pin "4") (pinfunction "STAT_4") (pintype "passive"))
    )
    (net (code "42") (name "unconnected-(U10-C-Pad3)") (class "Default")
      (node (ref "U10") (pin "3") (pinfunction "C_3") (pintype "passive"))
    )
  )
)
